# MCU_Power_Supply_Sheet.net
KiCad netlist of a schematic drawn in Altium Designer
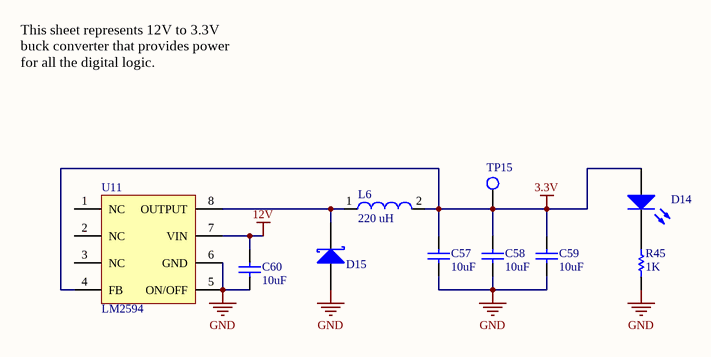
[diagram p0: MCU_Power_Supply_Sheet.SchDoc]

(export (version "E")
  (design (tool "Eeschema 10.0.6"))
  (components
    (comp (ref "C57")
      (value "10uF")
      (footprint "C1206")
      (description "Capacitor")
      (fields (field (name "MANUFACTURER PART NUMBER") "1206X106K250CT"))
      (libsource (lib "Kilian_UCC_Library") (part "C_1206_10uF_25V_CER"))
    )
    (comp (ref "C58")
      (value "10uF")
      (footprint "C1206")
      (description "Capacitor")
      (fields (field (name "MANUFACTURER PART NUMBER") "1206X106K250CT"))
      (libsource (lib "Kilian_UCC_Library") (part "C_1206_10uF_25V_CER"))
    )
    (comp (ref "C59")
      (value "10uF")
      (footprint "C1206")
      (description "Capacitor")
      (fields (field (name "MANUFACTURER PART NUMBER") "1206X106K250CT"))
      (libsource (lib "Kilian_UCC_Library") (part "C_1206_10uF_25V_CER"))
    )
    (comp (ref "C60")
      (value "10uF")
      (footprint "C1206")
      (description "Capacitor")
      (fields (field (name "MANUFACTURER PART NUMBER") "1206X106K250CT"))
      (libsource (lib "Kilian_UCC_Library") (part "C_1206_10uF_25V_CER"))
    )
    (comp (ref "D14")
      (value "Green_LED_150060GS75000")
      (footprint "Green_LED_150060GS75000")
      (description "WURTH ELEKTRONIK  150060GS75000  LED, Green, SMD, 30 mA, 3.2 V, 520 nm")
      (fields
        (field (name "MANUFACTURER PART NUMBER") "150060GS75000")
        (field (name "MANUFACTURER") "WURTH ELEKTRONIK")
      )
      (libsource (lib "Kilian_UCC_Library") (part "Green_LED_150060GS75000"))
    )
    (comp (ref "D15")
      (value "NRVTS245")
      (footprint "SOD123")
      (description "ON SEMICONDUCTOR  NRVTS245ESFT1G  Schottky Rectifier, Single, 45 V, 2 A, SOD-123, 2 Pins, 650 mV")
      (fields
        (field (name "MANUFACTURER PART NUMBER") "NRVTS245ESFT1G")
        (field (name "MANUFACTURER") "ON SEMICONDUCTOR")
      )
      (libsource (lib "Kilian_UCC_Library") (part "NRVTS245"))
    )
    (comp (ref "L6")
      (value "220 uH")
      (footprint "WE-TPC_1028")
      (description "WE-TPC SMD Shielded Tiny Power Inductor, Size 1028, 220 uH")
      (fields
        (field (name "MANUFACTURER") "Wurth Elektronik")
        (field (name "PARTNO.") "744065221")
        (field (name "CREATED BY") "Baojun Chen")
      )
      (libsource (lib "Kilian_UCC_Library") (part "WE-TPC 1028, 744065221"))
    )
    (comp (ref "R45")
      (value "1K")
      (footprint "0603")
      (description "Resistor")
      (fields
        (field (name "MANUFACTURER PART NUMBER") "ERJ3GEYJ102V")
        (field (name "MANUFACTURER") "PANASONIC ELECTRONIC COMPONENTS")
      )
      (libsource (lib "Kilian_UCC_Library") (part "R_0603_1k_75V_100mW"))
    )
    (comp (ref "TP15")
      (value "Test Point")
      (footprint "Test_Point")
      (description "HARWIN  S1751-46R  PCB Test Point, S1751 Series, Surface Mount, Copper Alloy, Tin Plated Contacts")
      (fields (field (name "MANUFACTURER") "HARWIN") (field (name "MANUFACTURER PART NUMBER") "S1751-46R"))
      (libsource (lib "Kilian_UCC_Library") (part "Test_Point"))
    )
    (comp (ref "U11")
      (value "LM2594")
      (footprint "D008_M")
      (fields
        (field (name "MANUFACTURER PART NUMBER") "LM2594M-3.3")
        (field (name "MANUFACTURER") "TEXAS INSTRUMENTS")
      )
      (libsource (lib "Kilian_UCC_Library") (part "LM2594"))
    )
  )
  (nets
    (net (code "1") (name "3.3V") (class "Default")
      (node (ref "C57") (pin "2") (pinfunction "2_2") (pintype "passive"))
      (node (ref "C58") (pin "2") (pinfunction "2_2") (pintype "passive"))
      (node (ref "C59") (pin "2") (pinfunction "2_2") (pintype "passive"))
      (node (ref "D14") (pin "2") (pinfunction "2_2") (pintype "passive"))
      (node (ref "L6") (pin "2") (pinfunction "2_2") (pintype "passive"))
      (node (ref "TP15") (pin "1") (pinfunction "TP_1") (pintype "passive"))
      (node (ref "U11") (pin "4") (pinfunction "FB_4") (pintype "passive"))
    )
    (net (code "2") (name "12V") (class "Default")
      (node (ref "C60") (pin "2") (pinfunction "2_2") (pintype "passive"))
      (node (ref "U11") (pin "7") (pinfunction "VIN_7") (pintype "passive"))
    )
    (net (code "3") (name "GND") (class "Default")
      (node (ref "C57") (pin "1") (pinfunction "1_1") (pintype "passive"))
      (node (ref "C58") (pin "1") (pinfunction "1_1") (pintype "passive"))
      (node (ref "C59") (pin "1") (pinfunction "1_1") (pintype "passive"))
      (node (ref "C60") (pin "1") (pinfunction "1_1") (pintype "passive"))
      (node (ref "D15") (pin "2") (pinfunction "2_2") (pintype "passive"))
      (node (ref "R45") (pin "1") (pinfunction "1_1") (pintype "passive"))
      (node (ref "U11") (pin "5") (pinfunction "ON/OFF_5") (pintype "passive"))
      (node (ref "U11") (pin "6") (pinfunction "GND_6") (pintype "passive"))
    )
    (net (code "4") (name "Net-(D14-Pad1)") (class "Default")
      (node (ref "D14") (pin "1") (pinfunction "1_1") (pintype "passive"))
      (node (ref "R45") (pin "2") (pinfunction "2_2") (pintype "passive"))
    )
    (net (code "5") (name "Net-(U11-OUTPUT)") (class "Default")
      (node (ref "D15") (pin "1") (pinfunction "1_1") (pintype "passive"))
      (node (ref "L6") (pin "1") (pinfunction "1_1") (pintype "passive"))
      (node (ref "U11") (pin "8") (pinfunction "OUTPUT_8") (pintype "passive"))
    )
    (net (code "6") (name "unconnected-(U11-NC-Pad1)") (class "Default")
      (node (ref "U11") (pin "1") (pinfunction "NC_1") (pintype "passive"))
    )
    (net (code "7") (name "unconnected-(U11-NC-Pad2)") (class "Default")
      (node (ref "U11") (pin "2") (pinfunction "NC_2") (pintype "passive"))
    )
    (net (code "8") (name "unconnected-(U11-NC-Pad3)") (class "Default")
      (node (ref "U11") (pin "3") (pinfunction "NC_3") (pintype "passive"))
    )
  )
)
